# placa_sensores_eagle.net
KiCad netlist of a schematic drawn in EAGLE
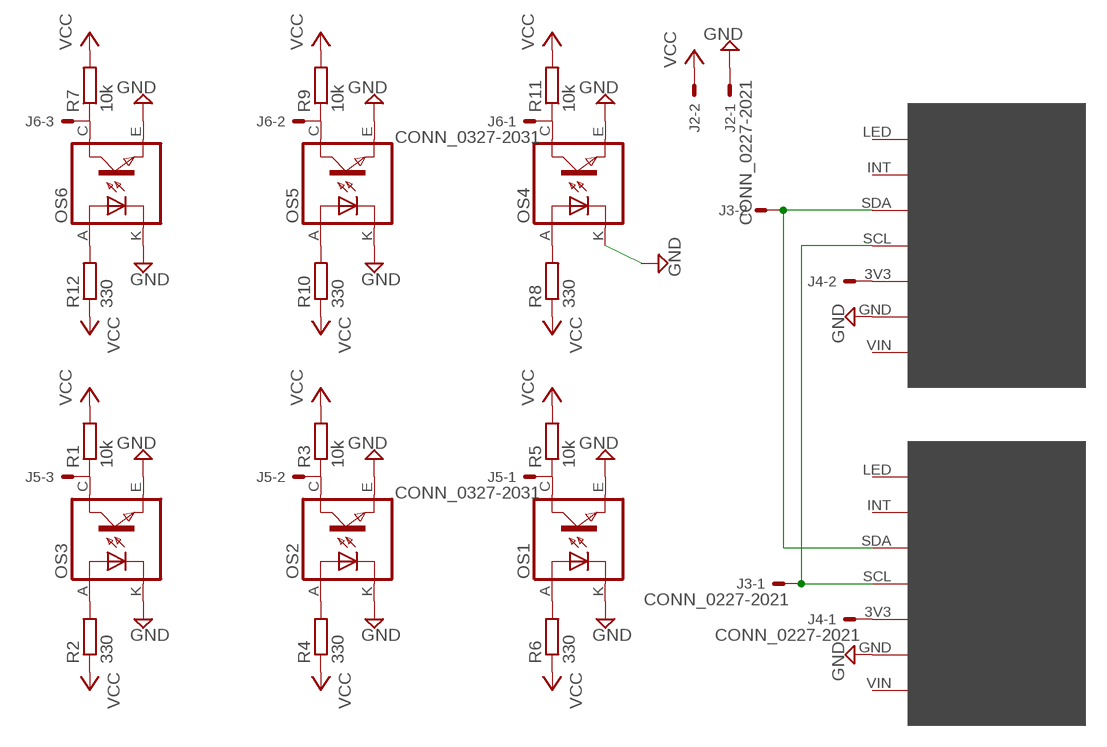
[diagram p0: schematic, sheet 1]

(export (version "E")
  (design (tool "Eeschema 10.0.6"))
  (components
    (comp (ref "J2")
      (value "CONN_0227-2021")
      (footprint "eagle-import:6410-02")
      (libsource (lib "eagle-import") (part "CONN_0227-2021"))
    )
    (comp (ref "J3")
      (value "CONN_0227-2021")
      (footprint "eagle-import:6410-02")
      (libsource (lib "eagle-import") (part "CONN_0227-2021"))
    )
    (comp (ref "J4")
      (value "CONN_0227-2021")
      (footprint "eagle-import:6410-02")
      (libsource (lib "eagle-import") (part "CONN_0227-2021"))
    )
    (comp (ref "J5")
      (value "CONN_0327-2031")
      (footprint "eagle-import:6410-03")
      (libsource (lib "eagle-import") (part "CONN_0327-2031"))
    )
    (comp (ref "J6")
      (value "CONN_0327-2031")
      (footprint "eagle-import:6410-03")
      (libsource (lib "eagle-import") (part "CONN_0327-2031"))
    )
    (comp (ref "OS1")
      (value "TCRT5000")
      (footprint "eagle-import:TCRT5000")
      (libsource (lib "eagle-import") (part "TCRT5000"))
    )
    (comp (ref "OS2")
      (value "TCRT5000")
      (footprint "eagle-import:TCRT5000")
      (libsource (lib "eagle-import") (part "TCRT5000"))
    )
    (comp (ref "OS3")
      (value "TCRT5000")
      (footprint "eagle-import:TCRT5000")
      (libsource (lib "eagle-import") (part "TCRT5000"))
    )
    (comp (ref "OS4")
      (value "TCRT5000")
      (footprint "eagle-import:TCRT5000")
      (libsource (lib "eagle-import") (part "TCRT5000"))
    )
    (comp (ref "OS5")
      (value "TCRT5000")
      (footprint "eagle-import:TCRT5000")
      (libsource (lib "eagle-import") (part "TCRT5000"))
    )
    (comp (ref "OS6")
      (value "TCRT5000")
      (footprint "eagle-import:TCRT5000")
      (libsource (lib "eagle-import") (part "TCRT5000"))
    )
    (comp (ref "R1")
      (value "10k")
      (footprint "eagle-import:0204_7")
      (libsource (lib "eagle-import") (part "R-EU_0204/7"))
    )
    (comp (ref "R2")
      (value "330")
      (footprint "eagle-import:0204_7")
      (libsource (lib "eagle-import") (part "R-EU_0204/7"))
    )
    (comp (ref "R3")
      (value "10k")
      (footprint "eagle-import:0204_7")
      (libsource (lib "eagle-import") (part "R-EU_0204/7"))
    )
    (comp (ref "R4")
      (value "330")
      (footprint "eagle-import:0204_7")
      (libsource (lib "eagle-import") (part "R-EU_0204/7"))
    )
    (comp (ref "R5")
      (value "10k")
      (footprint "eagle-import:0204_7")
      (libsource (lib "eagle-import") (part "R-EU_0204/7"))
    )
    (comp (ref "R6")
      (value "330")
      (footprint "eagle-import:0204_7")
      (libsource (lib "eagle-import") (part "R-EU_0204/7"))
    )
    (comp (ref "R7")
      (value "10k")
      (footprint "eagle-import:0204_7")
      (libsource (lib "eagle-import") (part "R-EU_0204/7"))
    )
    (comp (ref "R8")
      (value "330")
      (footprint "eagle-import:0204_7")
      (libsource (lib "eagle-import") (part "R-EU_0204/7"))
    )
    (comp (ref "R9")
      (value "10k")
      (footprint "eagle-import:0204_7")
      (libsource (lib "eagle-import") (part "R-EU_0204/7"))
    )
    (comp (ref "R10")
      (value "330")
      (footprint "eagle-import:0204_7")
      (libsource (lib "eagle-import") (part "R-EU_0204/7"))
    )
    (comp (ref "R11")
      (value "10k")
      (footprint "eagle-import:0204_7")
      (libsource (lib "eagle-import") (part "R-EU_0204/7"))
    )
    (comp (ref "R12")
      (value "330")
      (footprint "eagle-import:0204_7")
      (libsource (lib "eagle-import") (part "R-EU_0204/7"))
    )
    (comp (ref "TCS1")
      (value "TCS34725")
      (footprint "eagle-import:TCS34725")
      (libsource (lib "eagle-import") (part "TCS34725"))
    )
    (comp (ref "TCS2")
      (value "TCS34725")
      (footprint "eagle-import:TCS34725")
      (libsource (lib "eagle-import") (part "TCS34725"))
    )
  )
  (nets
    (net (code "1") (name "GND") (class "Default")
      (node (ref "J2") (pin "1") (pinfunction "S_1") (pintype "passive"))
      (node (ref "OS1") (pin "E") (pinfunction "EMITTER_E") (pintype "passive"))
      (node (ref "OS1") (pin "K") (pinfunction "CATHODE_K") (pintype "passive"))
      (node (ref "OS2") (pin "E") (pinfunction "EMITTER_E") (pintype "passive"))
      (node (ref "OS2") (pin "K") (pinfunction "CATHODE_K") (pintype "passive"))
      (node (ref "OS3") (pin "E") (pinfunction "EMITTER_E") (pintype "passive"))
      (node (ref "OS3") (pin "K") (pinfunction "CATHODE_K") (pintype "passive"))
      (node (ref "OS4") (pin "E") (pinfunction "EMITTER_E") (pintype "passive"))
      (node (ref "OS4") (pin "K") (pinfunction "CATHODE_K") (pintype "passive"))
      (node (ref "OS5") (pin "E") (pinfunction "EMITTER_E") (pintype "passive"))
      (node (ref "OS5") (pin "K") (pinfunction "CATHODE_K") (pintype "passive"))
      (node (ref "OS6") (pin "E") (pinfunction "EMITTER_E") (pintype "passive"))
      (node (ref "OS6") (pin "K") (pinfunction "CATHODE_K") (pintype "passive"))
      (node (ref "TCS1") (pin "GND") (pinfunction "GND_GND") (pintype "bidirectional"))
      (node (ref "TCS2") (pin "GND") (pinfunction "GND_GND") (pintype "bidirectional"))
    )
    (net (code "2") (name "Net-(J3A-S)") (class "Default")
      (node (ref "J3") (pin "1") (pinfunction "S_1") (pintype "passive"))
      (node (ref "TCS1") (pin "SCL") (pinfunction "SCL_SCL") (pintype "bidirectional"))
      (node (ref "TCS2") (pin "SCL") (pinfunction "SCL_SCL") (pintype "bidirectional"))
    )
    (net (code "3") (name "Net-(J3B-S)") (class "Default")
      (node (ref "J3") (pin "2") (pinfunction "S_2") (pintype "passive"))
      (node (ref "TCS1") (pin "SDA") (pinfunction "SDA_SDA") (pintype "bidirectional"))
      (node (ref "TCS2") (pin "SDA") (pinfunction "SDA_SDA") (pintype "bidirectional"))
    )
    (net (code "4") (name "Net-(J4A-S)") (class "Default")
      (node (ref "J4") (pin "1") (pinfunction "S_1") (pintype "passive"))
      (node (ref "TCS2") (pin "3V3") (pinfunction "3V3_3V3") (pintype "bidirectional"))
    )
    (net (code "5") (name "Net-(J4B-S)") (class "Default")
      (node (ref "J4") (pin "2") (pinfunction "S_2") (pintype "passive"))
      (node (ref "TCS1") (pin "3V3") (pinfunction "3V3_3V3") (pintype "bidirectional"))
    )
    (net (code "6") (name "Net-(J5A-S)") (class "Default")
      (node (ref "J5") (pin "1") (pinfunction "S_1") (pintype "passive"))
      (node (ref "OS1") (pin "C") (pinfunction "COLLECTOR_C") (pintype "passive"))
      (node (ref "R5") (pin "1") (pinfunction "1_1") (pintype "passive"))
    )
    (net (code "7") (name "Net-(J5B-S)") (class "Default")
      (node (ref "J5") (pin "2") (pinfunction "S_2") (pintype "passive"))
      (node (ref "OS2") (pin "C") (pinfunction "COLLECTOR_C") (pintype "passive"))
      (node (ref "R3") (pin "1") (pinfunction "1_1") (pintype "passive"))
    )
    (net (code "8") (name "Net-(J5C-S)") (class "Default")
      (node (ref "J5") (pin "3") (pinfunction "S_3") (pintype "passive"))
      (node (ref "OS3") (pin "C") (pinfunction "COLLECTOR_C") (pintype "passive"))
      (node (ref "R1") (pin "1") (pinfunction "1_1") (pintype "passive"))
    )
    (net (code "9") (name "Net-(J6A-S)") (class "Default")
      (node (ref "J6") (pin "1") (pinfunction "S_1") (pintype "passive"))
      (node (ref "OS4") (pin "C") (pinfunction "COLLECTOR_C") (pintype "passive"))
      (node (ref "R11") (pin "1") (pinfunction "1_1") (pintype "passive"))
    )
    (net (code "10") (name "Net-(J6B-S)") (class "Default")
      (node (ref "J6") (pin "2") (pinfunction "S_2") (pintype "passive"))
      (node (ref "OS5") (pin "C") (pinfunction "COLLECTOR_C") (pintype "passive"))
      (node (ref "R9") (pin "1") (pinfunction "1_1") (pintype "passive"))
    )
    (net (code "11") (name "Net-(J6C-S)") (class "Default")
      (node (ref "J6") (pin "3") (pinfunction "S_3") (pintype "passive"))
      (node (ref "OS6") (pin "C") (pinfunction "COLLECTOR_C") (pintype "passive"))
      (node (ref "R7") (pin "1") (pinfunction "1_1") (pintype "passive"))
    )
    (net (code "12") (name "Net-(OS1-ANODE)") (class "Default")
      (node (ref "OS1") (pin "A") (pinfunction "ANODE_A") (pintype "passive"))
      (node (ref "R6") (pin "2") (pinfunction "2_2") (pintype "passive"))
    )
    (net (code "13") (name "Net-(OS2-ANODE)") (class "Default")
      (node (ref "OS2") (pin "A") (pinfunction "ANODE_A") (pintype "passive"))
      (node (ref "R4") (pin "2") (pinfunction "2_2") (pintype "passive"))
    )
    (net (code "14") (name "Net-(OS3-ANODE)") (class "Default")
      (node (ref "OS3") (pin "A") (pinfunction "ANODE_A") (pintype "passive"))
      (node (ref "R2") (pin "2") (pinfunction "2_2") (pintype "passive"))
    )
    (net (code "15") (name "Net-(OS4-ANODE)") (class "Default")
      (node (ref "OS4") (pin "A") (pinfunction "ANODE_A") (pintype "passive"))
      (node (ref "R8") (pin "2") (pinfunction "2_2") (pintype "passive"))
    )
    (net (code "16") (name "Net-(OS5-ANODE)") (class "Default")
      (node (ref "OS5") (pin "A") (pinfunction "ANODE_A") (pintype "passive"))
      (node (ref "R10") (pin "2") (pinfunction "2_2") (pintype "passive"))
    )
    (net (code "17") (name "Net-(OS6-ANODE)") (class "Default")
      (node (ref "OS6") (pin "A") (pinfunction "ANODE_A") (pintype "passive"))
      (node (ref "R12") (pin "2") (pinfunction "2_2") (pintype "passive"))
    )
    (net (code "18") (name "VCC") (class "Default")
      (node (ref "J2") (pin "2") (pinfunction "S_2") (pintype "passive"))
      (node (ref "R1") (pin "2") (pinfunction "2_2") (pintype "passive"))
      (node (ref "R10") (pin "1") (pinfunction "1_1") (pintype "passive"))
      (node (ref "R11") (pin "2") (pinfunction "2_2") (pintype "passive"))
      (node (ref "R12") (pin "1") (pinfunction "1_1") (pintype "passive"))
      (node (ref "R2") (pin "1") (pinfunction "1_1") (pintype "passive"))
      (node (ref "R3") (pin "2") (pinfunction "2_2") (pintype "passive"))
      (node (ref "R4") (pin "1") (pinfunction "1_1") (pintype "passive"))
      (node (ref "R5") (pin "2") (pinfunction "2_2") (pintype "passive"))
      (node (ref "R6") (pin "1") (pinfunction "1_1") (pintype "passive"))
      (node (ref "R7") (pin "2") (pinfunction "2_2") (pintype "passive"))
      (node (ref "R8") (pin "1") (pinfunction "1_1") (pintype "passive"))
      (node (ref "R9") (pin "2") (pinfunction "2_2") (pintype "passive"))
    )
    (net (code "19") (name "unconnected-(TCS1-PadINT)") (class "Default")
      (node (ref "TCS1") (pin "INT") (pinfunction "INT_INT") (pintype "bidirectional"))
    )
    (net (code "20") (name "unconnected-(TCS1-PadLED)") (class "Default")
      (node (ref "TCS1") (pin "LED") (pinfunction "LED_LED") (pintype "bidirectional"))
    )
    (net (code "21") (name "unconnected-(TCS1-PadVIN)") (class "Default")
      (node (ref "TCS1") (pin "VIN") (pinfunction "VIN_VIN") (pintype "bidirectional"))
    )
    (net (code "22") (name "unconnected-(TCS2-PadINT)") (class "Default")
      (node (ref "TCS2") (pin "INT") (pinfunction "INT_INT") (pintype "bidirectional"))
    )
    (net (code "23") (name "unconnected-(TCS2-PadLED)") (class "Default")
      (node (ref "TCS2") (pin "LED") (pinfunction "LED_LED") (pintype "bidirectional"))
    )
    (net (code "24") (name "unconnected-(TCS2-PadVIN)") (class "Default")
      (node (ref "TCS2") (pin "VIN") (pinfunction "VIN_VIN") (pintype "bidirectional"))
    )
  )
)
